# Breadboard_ICSP.net
KiCad netlist of a schematic drawn in EAGLE
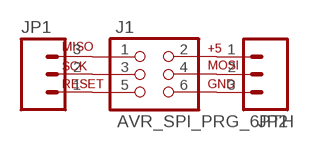
[diagram p0: schematic, sheet 1]

(export (version "E")
  (design (tool "Eeschema 10.0.6"))
  (components
    (comp (ref "J1")
      (value "AVR_SPI_PRG_6PTH")
      (footprint "eagle-import:2X3")
      (libsource (lib "eagle-import") (part "AVR_SPI_PRG_6PTH"))
    )
    (comp (ref "JP1")
      (value "M03PTH")
      (footprint "eagle-import:1X03")
      (libsource (lib "eagle-import") (part "M03PTH"))
    )
    (comp (ref "JP2")
      (value "M03PTH")
      (footprint "eagle-import:1X03")
      (libsource (lib "eagle-import") (part "M03PTH"))
    )
  )
  (nets
    (net (code "1") (name "Net-(J1-Pad1)") (class "Default")
      (node (ref "J1") (pin "1") (pinfunction "1_1") (pintype "passive"))
      (node (ref "JP1") (pin "3") (pinfunction "3_3") (pintype "passive"))
    )
    (net (code "2") (name "Net-(J1-Pad2)") (class "Default")
      (node (ref "J1") (pin "2") (pinfunction "2_2") (pintype "passive"))
      (node (ref "JP2") (pin "1") (pinfunction "1_1") (pintype "passive"))
    )
    (net (code "3") (name "Net-(J1-Pad3)") (class "Default")
      (node (ref "J1") (pin "3") (pinfunction "3_3") (pintype "passive"))
      (node (ref "JP1") (pin "2") (pinfunction "2_2") (pintype "passive"))
    )
    (net (code "4") (name "Net-(J1-Pad4)") (class "Default")
      (node (ref "J1") (pin "4") (pinfunction "4_4") (pintype "passive"))
      (node (ref "JP2") (pin "2") (pinfunction "2_2") (pintype "passive"))
    )
    (net (code "5") (name "Net-(J1-Pad5)") (class "Default")
      (node (ref "J1") (pin "5") (pinfunction "5_5") (pintype "passive"))
      (node (ref "JP1") (pin "1") (pinfunction "1_1") (pintype "passive"))
    )
    (net (code "6") (name "Net-(J1-Pad6)") (class "Default")
      (node (ref "J1") (pin "6") (pinfunction "6_6") (pintype "passive"))
      (node (ref "JP2") (pin "3") (pinfunction "3_3") (pintype "passive"))
    )
  )
)
